# MCU_Power_Clock_Debug.net
KiCad netlist of a schematic drawn in Altium Designer
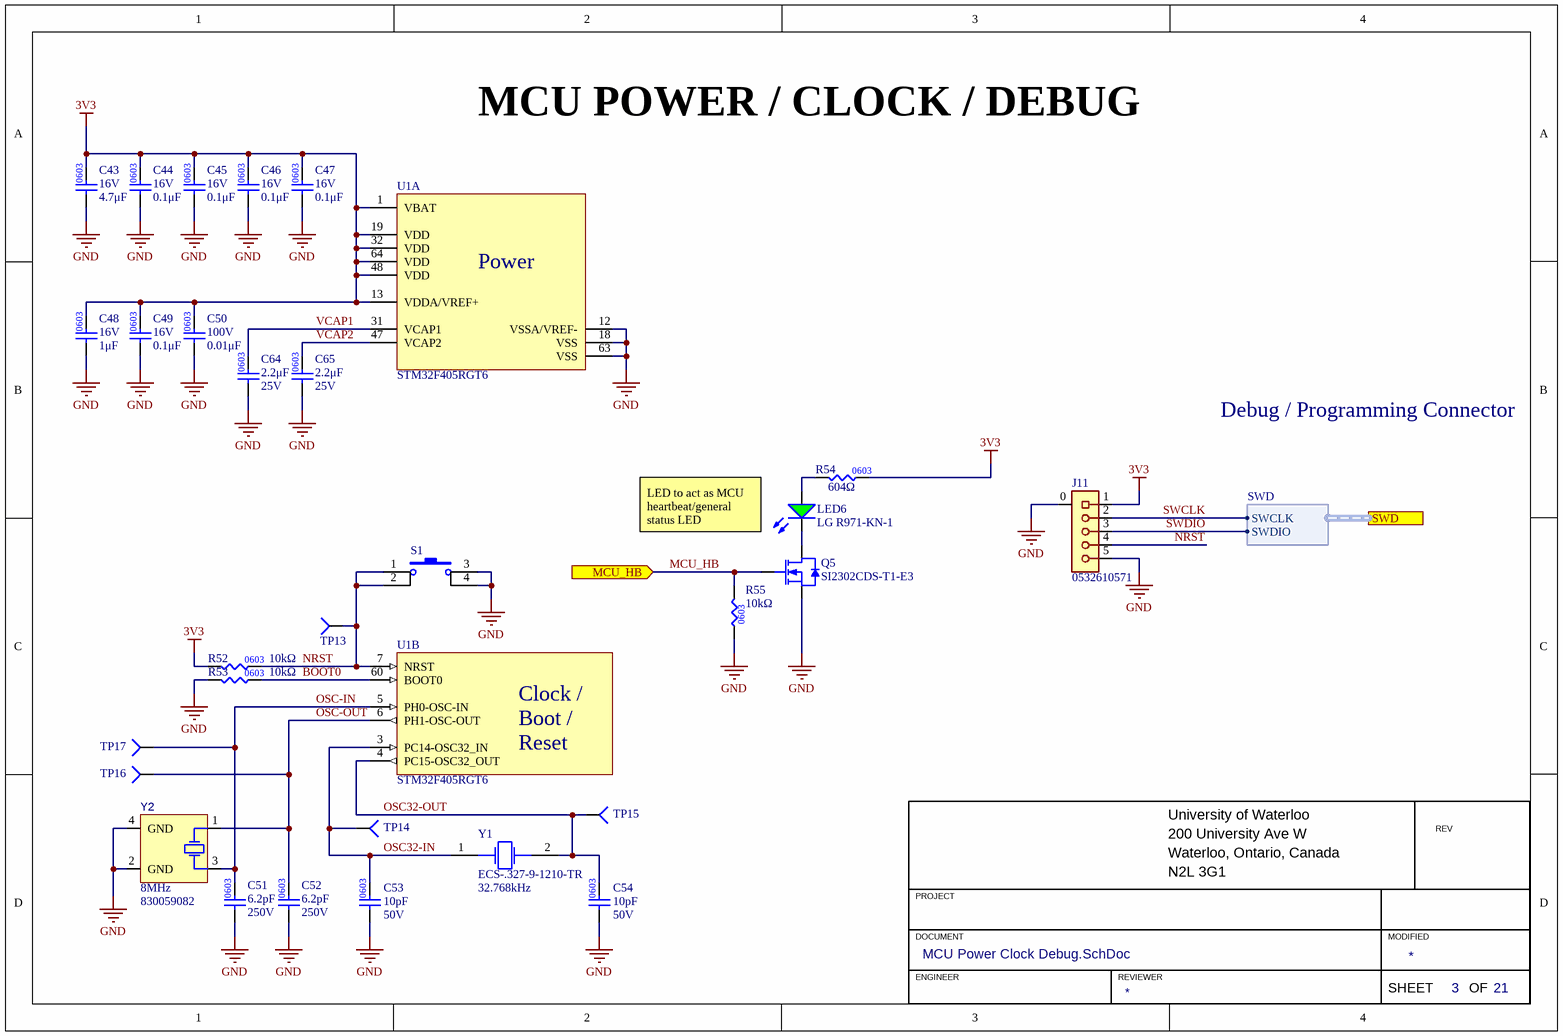
[diagram p0: MCU Power Clock Debug.SchDoc]

(export (version "E")
  (design (tool "Eeschema 10.0.6"))
  (components
    (comp (ref "C43")
      (value "4.7μF")
      (footprint "CAP0603")
      (description "CAP CER 4.7UF 16V X6S 0603")
      (fields (field (name "VOLTAGE RATING") "16V") (field (name "Comment") "CAP_4.7uF_16V_0603"))
      (libsource (lib "Personal_Schematic_Library_2022") (part "CAP_4.7uF_16V_0603"))
    )
    (comp (ref "C44")
      (value "0.1μF")
      (footprint "CAP0603")
      (description "CAP CER 0.1UF 16V X7R 0603")
      (fields (field (name "VOLTAGE RATING") "16V") (field (name "Comment") "CAP_0.1uF_16V_0603"))
      (libsource (lib "Personal_Schematic_Library_2022") (part "CAP_0.1uF_16V_0603"))
    )
    (comp (ref "C45")
      (value "0.1μF")
      (footprint "CAP0603")
      (description "CAP CER 0.1UF 16V X7R 0603")
      (fields (field (name "VOLTAGE RATING") "16V") (field (name "Comment") "CAP_0.1uF_16V_0603"))
      (libsource (lib "Personal_Schematic_Library_2022") (part "CAP_0.1uF_16V_0603"))
    )
    (comp (ref "C46")
      (value "0.1μF")
      (footprint "CAP0603")
      (description "CAP CER 0.1UF 16V X7R 0603")
      (fields (field (name "VOLTAGE RATING") "16V") (field (name "Comment") "CAP_0.1uF_16V_0603"))
      (libsource (lib "Personal_Schematic_Library_2022") (part "CAP_0.1uF_16V_0603"))
    )
    (comp (ref "C47")
      (value "0.1μF")
      (footprint "CAP0603")
      (description "CAP CER 0.1UF 16V X7R 0603")
      (fields (field (name "VOLTAGE RATING") "16V") (field (name "Comment") "CAP_0.1uF_16V_0603"))
      (libsource (lib "Personal_Schematic_Library_2022") (part "CAP_0.1uF_16V_0603"))
    )
    (comp (ref "C48")
      (value "1μF")
      (footprint "CAP0603")
      (description "CAP CER 1UF 16V X7R 0603")
      (fields (field (name "VOLTAGE RATING") "16V") (field (name "Comment") "CAP_1uF_16V_0603"))
      (libsource (lib "Personal_Schematic_Library_2022") (part "CAP_1uF_16V_0603"))
    )
    (comp (ref "C49")
      (value "0.1μF")
      (footprint "CAP0603")
      (description "CAP CER 0.1UF 16V X7R 0603")
      (fields (field (name "VOLTAGE RATING") "16V") (field (name "Comment") "CAP_0.1uF_16V_0603"))
      (libsource (lib "Personal_Schematic_Library_2022") (part "CAP_0.1uF_16V_0603"))
    )
    (comp (ref "C50")
      (value "0.01μF")
      (footprint "CAP0603")
      (description "CAP CER 0.01uF 100V X7R 0603")
      (fields (field (name "VOLTAGE RATING") "100V") (field (name "Comment") "CAP_0.01uF_100V_0603"))
      (libsource (lib "Personal_Schematic_Library_2022") (part "CAP_0.01uF_100V_0603"))
    )
    (comp (ref "C51")
      (value "6.2pF")
      (footprint "CAP0603")
      (description "HVCAP0603 COG 6.2PF .25PF 250V")
      (fields (field (name "VOLTAGE RATING") "250V") (field (name "Comment") "CAP_6.2pF_250V_0603"))
      (libsource (lib "Personal_Schematic_Library_2022") (part "CAP_6.2pF_250V_0603"))
    )
    (comp (ref "C52")
      (value "6.2pF")
      (footprint "CAP0603")
      (description "HVCAP0603 COG 6.2PF .25PF 250V")
      (fields (field (name "VOLTAGE RATING") "250V") (field (name "Comment") "CAP_6.2pF_250V_0603"))
      (libsource (lib "Personal_Schematic_Library_2022") (part "CAP_6.2pF_250V_0603"))
    )
    (comp (ref "C53")
      (value "10pF")
      (footprint "CAP0603")
      (description "CAP CER 10PF 50V X7R 0603")
      (fields (field (name "VOLTAGE RATING") "50V") (field (name "Comment") "CAP_10pF_50V_0603"))
      (libsource (lib "Personal_Schematic_Library_2022") (part "CAP_10pF_50V_0603"))
    )
    (comp (ref "C54")
      (value "10pF")
      (footprint "CAP0603")
      (description "CAP CER 10PF 50V X7R 0603")
      (fields (field (name "VOLTAGE RATING") "50V") (field (name "Comment") "CAP_10pF_50V_0603"))
      (libsource (lib "Personal_Schematic_Library_2022") (part "CAP_10pF_50V_0603"))
    )
    (comp (ref "C64")
      (value "2.2μF")
      (footprint "CAP0603")
      (description "CAP CER 2.2UF 25V X5R 0603")
      (fields (field (name "VOLTAGE RATING") "25V") (field (name "Comment") "CAP_2.2uF_25V_0603"))
      (libsource (lib "Personal_Schematic_Library_2022") (part "CAP_2.2uF_25V_0603"))
    )
    (comp (ref "C65")
      (value "2.2μF")
      (footprint "CAP0603")
      (description "CAP CER 2.2UF 25V X5R 0603")
      (fields (field (name "VOLTAGE RATING") "25V") (field (name "Comment") "CAP_2.2uF_25V_0603"))
      (libsource (lib "Personal_Schematic_Library_2022") (part "CAP_2.2uF_25V_0603"))
    )
    (comp (ref "J11")
      (value "CON_MOLEX-PICO_5POS_RA")
      (footprint "MOLEX-532610571")
      (description "CONN HEADER SMD R/A 5POS 1.25MM")
      (fields (field (name "MANUFACTURER PART NUMBER 1") "0532610571"))
      (libsource (lib "Personal_Schematic_Library_2022") (part "CON_MOLEX-PICO_5POS_RA"))
    )
    (comp (ref "LED6")
      (value "LED_GREEN")
      (footprint "LED_0805_GREEN")
      (description "LED GREEN DIFFUSED 0805 SMD")
      (fields (field (name "MANUFACTURER PART NUMBER 1") "LG R971-KN-1"))
      (libsource (lib "Personal_Schematic_Library_2022") (part "LED_GREEN"))
    )
    (comp (ref "Q5")
      (value "NMOS_20V_6A")
      (footprint "SOT23-3")
      (description "MOSFET N-CH 20V 2.6A SOT23-3")
      (fields (field (name "MANUFACTURER PART NUMBER 1") "SI2302CDS-T1-E3"))
      (libsource (lib "Personal_Schematic_Library_2022") (part "NMOS_20V_2.6A"))
    )
    (comp (ref "R52")
      (value "10kΩ")
      (footprint "RES0603")
      (description "RES 10K OHM 1% 1/8W 0603")
      (fields (field (name "Comment") "RES_10kΩ_0603_1%"))
      (libsource (lib "Personal_Schematic_Library_2022") (part "RES_10kΩ_0603_1%"))
    )
    (comp (ref "R53")
      (value "10kΩ")
      (footprint "RES0603")
      (description "RES 10K OHM 1% 1/8W 0603")
      (fields (field (name "Comment") "RES_10kΩ_0603_1%"))
      (libsource (lib "Personal_Schematic_Library_2022") (part "RES_10kΩ_0603_1%"))
    )
    (comp (ref "R54")
      (value "604Ω")
      (footprint "RES0603")
      (description "RES 604 OHM 1% 1/10W 0603")
      (fields (field (name "Comment") "RES_604Ω_0603_1%"))
      (libsource (lib "Personal_Schematic_Library_2022") (part "RES_604Ω_0603_1%"))
    )
    (comp (ref "R55")
      (value "10kΩ")
      (footprint "RES0603")
      (description "RES 10K OHM 1% 1/8W 0603")
      (fields (field (name "Comment") "RES_10kΩ_0603_1%"))
      (libsource (lib "Personal_Schematic_Library_2022") (part "RES_10kΩ_0603_1%"))
    )
    (comp (ref "S1")
      (value "SW_SPST_NO_4.5x4.5")
      (footprint "SPST_PUSHBUTTON_TL3305AF260QG")
      (description "SWITCH TACTILE SPST-NO 50MA 12V")
      (libsource (lib "Personal_Schematic_Library_2022") (part "SW_SPST_NO_4.5x4.5"))
    )
    (comp (ref "TP13")
      (value "TESTPOINT_1MM_CIRCLE")
      (footprint "TESTPOINT_CIRCLE_1MM")
      (description "TESTPOINT 1MM CIRCLE")
      (libsource (lib "Personal_Schematic_Library_2022") (part "TESTPOINT_1MM_CIRCLE"))
    )
    (comp (ref "TP14")
      (value "TESTPOINT_1MM_CIRCLE")
      (footprint "TESTPOINT_CIRCLE_1MM")
      (description "TESTPOINT 1MM CIRCLE")
      (libsource (lib "Personal_Schematic_Library_2022") (part "TESTPOINT_1MM_CIRCLE"))
    )
    (comp (ref "TP15")
      (value "TESTPOINT_1MM_CIRCLE")
      (footprint "TESTPOINT_CIRCLE_1MM")
      (description "TESTPOINT 1MM CIRCLE")
      (libsource (lib "Personal_Schematic_Library_2022") (part "TESTPOINT_1MM_CIRCLE"))
    )
    (comp (ref "TP16")
      (value "TESTPOINT_1MM_CIRCLE")
      (footprint "TESTPOINT_CIRCLE_1MM")
      (description "TESTPOINT 1MM CIRCLE")
      (libsource (lib "Personal_Schematic_Library_2022") (part "TESTPOINT_1MM_CIRCLE"))
    )
    (comp (ref "TP17")
      (value "TESTPOINT_1MM_CIRCLE")
      (footprint "TESTPOINT_CIRCLE_1MM")
      (description "TESTPOINT 1MM CIRCLE")
      (libsource (lib "Personal_Schematic_Library_2022") (part "TESTPOINT_1MM_CIRCLE"))
    )
    (comp (ref "U1")
      (value "STM32F405RGT6")
      (footprint "STM_LQFP64")
      (description "IC MCU 32BIT 1MB FLASH 64LQFP")
      (libsource (lib "Personal_Schematic_Library_2022") (part "STM32F405RGT6"))
    )
    (comp (ref "Y1")
      (value "CRYSTAL_32.768KHZ")
      (footprint "OSC_ECS-327TR-2")
      (description "CRYSTAL 32.7680KHZ 9PF SMD")
      (fields
        (field (name "FREQUENCY") "32.768kHz")
        (field (name "MANUFACTURER PART NUMBER 1") "ECS-.327-9-1210-TR")
      )
      (libsource (lib "Personal_Schematic_Library_2022") (part "CRYSTAL_32.768KHZ"))
    )
    (comp (ref "Y2")
      (value "CRYSTAL_8MHZ_8PF")
      (footprint "XTAL_WURTH_830059082")
      (description "WE-XTAL QUARTZ CRYSTAL 8.0 MHZ;")
      (fields (field (name "FREQUENCY") "8MHz") (field (name "MANUFACTURER PART NUMBER 1") "830059082"))
      (libsource (lib "Personal_Schematic_Library_2022") (part "CRYSTAL_8MHZ_8PF"))
    )
  )
  (nets
    (net (code "2") (name "/BOOT0") (class "Default")
      (node (ref "R53") (pin "2") (pinfunction "2_2") (pintype "passive"))
      (node (ref "U1") (pin "60") (pinfunction "BOOT0_60") (pintype "input"))
    )
    (net (code "3") (name "/MCU_HB") (class "Default")
      (node (ref "Q5") (pin "1") (pinfunction "GATE_1") (pintype "passive"))
      (node (ref "R55") (pin "2") (pinfunction "2_2") (pintype "passive"))
    )
    (net (code "4") (name "/NRST") (class "Default")
      (node (ref "J11") (pin "4") (pinfunction "4_4") (pintype "passive"))
      (node (ref "R52") (pin "2") (pinfunction "2_2") (pintype "passive"))
      (node (ref "S1") (pin "1") (pinfunction "1_1") (pintype "passive"))
      (node (ref "S1") (pin "2") (pinfunction "2_2") (pintype "passive"))
      (node (ref "TP13") (pin "1") (pinfunction "=value_1") (pintype "passive"))
      (node (ref "U1") (pin "7") (pinfunction "NRST_7") (pintype "input"))
    )
    (net (code "5") (name "/OSC-IN") (class "Default")
      (node (ref "C51") (pin "2") (pinfunction "2_2") (pintype "passive"))
      (node (ref "TP17") (pin "1") (pinfunction "=value_1") (pintype "passive"))
      (node (ref "U1") (pin "5") (pinfunction "PH0-OSC-IN_5") (pintype "input"))
      (node (ref "Y2") (pin "3") (pinfunction "HOT_3") (pintype "passive"))
    )
    (net (code "6") (name "/OSC-OUT") (class "Default")
      (node (ref "C52") (pin "2") (pinfunction "2_2") (pintype "passive"))
      (node (ref "TP16") (pin "1") (pinfunction "=value_1") (pintype "passive"))
      (node (ref "U1") (pin "6") (pinfunction "PH1-OSC-OUT_6") (pintype "output"))
      (node (ref "Y2") (pin "1") (pinfunction "HOT_1") (pintype "passive"))
    )
    (net (code "7") (name "/OSC32-IN") (class "Default")
      (node (ref "C53") (pin "2") (pinfunction "2_2") (pintype "passive"))
      (node (ref "TP14") (pin "1") (pinfunction "=value_1") (pintype "passive"))
      (node (ref "U1") (pin "3") (pinfunction "PC14-OSC32_IN_3") (pintype "input"))
      (node (ref "Y1") (pin "1") (pinfunction "1_1") (pintype "passive"))
    )
    (net (code "8") (name "/OSC32-OUT") (class "Default")
      (node (ref "C54") (pin "2") (pinfunction "2_2") (pintype "passive"))
      (node (ref "TP15") (pin "1") (pinfunction "=value_1") (pintype "passive"))
      (node (ref "U1") (pin "4") (pinfunction "PC15-OSC32_OUT_4") (pintype "output"))
      (node (ref "Y1") (pin "2") (pinfunction "2_2") (pintype "passive"))
    )
    (net (code "9") (name "/SWCLK") (class "Default")
      (node (ref "J11") (pin "2") (pinfunction "2_2") (pintype "passive"))
    )
    (net (code "10") (name "/SWDIO") (class "Default")
      (node (ref "J11") (pin "3") (pinfunction "3_3") (pintype "passive"))
    )
    (net (code "11") (name "/VCAP1") (class "Default")
      (node (ref "C64") (pin "2") (pinfunction "2_2") (pintype "passive"))
      (node (ref "U1") (pin "31") (pinfunction "VCAP1_31") (pintype "power_in"))
    )
    (net (code "12") (name "/VCAP2") (class "Default")
      (node (ref "C65") (pin "2") (pinfunction "2_2") (pintype "passive"))
      (node (ref "U1") (pin "47") (pinfunction "VCAP2_47") (pintype "power_in"))
    )
    (net (code "14") (name "3V3") (class "Default")
      (node (ref "C43") (pin "2") (pinfunction "2_2") (pintype "passive"))
      (node (ref "C44") (pin "2") (pinfunction "2_2") (pintype "passive"))
      (node (ref "C45") (pin "2") (pinfunction "2_2") (pintype "passive"))
      (node (ref "C46") (pin "2") (pinfunction "2_2") (pintype "passive"))
      (node (ref "C47") (pin "2") (pinfunction "2_2") (pintype "passive"))
      (node (ref "C48") (pin "2") (pinfunction "2_2") (pintype "passive"))
      (node (ref "C49") (pin "2") (pinfunction "2_2") (pintype "passive"))
      (node (ref "C50") (pin "2") (pinfunction "2_2") (pintype "passive"))
      (node (ref "J11") (pin "1") (pinfunction "1_1") (pintype "passive"))
      (node (ref "R52") (pin "1") (pinfunction "1_1") (pintype "passive"))
      (node (ref "R54") (pin "2") (pinfunction "2_2") (pintype "passive"))
      (node (ref "U1") (pin "1") (pinfunction "VBAT_1") (pintype "power_in"))
      (node (ref "U1") (pin "13") (pinfunction "VDDA/VREF+_13") (pintype "power_in"))
      (node (ref "U1") (pin "19") (pinfunction "VDD_19") (pintype "power_in"))
      (node (ref "U1") (pin "32") (pinfunction "VDD_32") (pintype "power_in"))
      (node (ref "U1") (pin "48") (pinfunction "VDD_48") (pintype "power_in"))
      (node (ref "U1") (pin "64") (pinfunction "VDD_64") (pintype "power_in"))
    )
    (net (code "15") (name "GND") (class "Default")
      (node (ref "C43") (pin "1") (pinfunction "1_1") (pintype "passive"))
      (node (ref "C44") (pin "1") (pinfunction "1_1") (pintype "passive"))
      (node (ref "C45") (pin "1") (pinfunction "1_1") (pintype "passive"))
      (node (ref "C46") (pin "1") (pinfunction "1_1") (pintype "passive"))
      (node (ref "C47") (pin "1") (pinfunction "1_1") (pintype "passive"))
      (node (ref "C48") (pin "1") (pinfunction "1_1") (pintype "passive"))
      (node (ref "C49") (pin "1") (pinfunction "1_1") (pintype "passive"))
      (node (ref "C50") (pin "1") (pinfunction "1_1") (pintype "passive"))
      (node (ref "C51") (pin "1") (pinfunction "1_1") (pintype "passive"))
      (node (ref "C52") (pin "1") (pinfunction "1_1") (pintype "passive"))
      (node (ref "C53") (pin "1") (pinfunction "1_1") (pintype "passive"))
      (node (ref "C54") (pin "1") (pinfunction "1_1") (pintype "passive"))
      (node (ref "C64") (pin "1") (pinfunction "1_1") (pintype "passive"))
      (node (ref "C65") (pin "1") (pinfunction "1_1") (pintype "passive"))
      (node (ref "J11") (pin "0") (pinfunction "0_0") (pintype "passive"))
      (node (ref "J11") (pin "5") (pinfunction "5_5") (pintype "passive"))
      (node (ref "Q5") (pin "2") (pinfunction "SOURCE_2") (pintype "passive"))
      (node (ref "R53") (pin "1") (pinfunction "1_1") (pintype "passive"))
      (node (ref "R55") (pin "1") (pinfunction "1_1") (pintype "passive"))
      (node (ref "S1") (pin "3") (pinfunction "3_3") (pintype "passive"))
      (node (ref "S1") (pin "4") (pinfunction "4_4") (pintype "passive"))
      (node (ref "U1") (pin "12") (pinfunction "VSSA/VREF-_12") (pintype "power_in"))
      (node (ref "U1") (pin "18") (pinfunction "VSS_18") (pintype "power_in"))
      (node (ref "U1") (pin "63") (pinfunction "VSS_63") (pintype "power_in"))
      (node (ref "Y2") (pin "2") (pinfunction "GND_2") (pintype "power_in"))
      (node (ref "Y2") (pin "4") (pinfunction "GND_4") (pintype "power_in"))
    )
    (net (code "16") (name "Net-(LED6-A)") (class "Default")
      (node (ref "LED6") (pin "1") (pinfunction "A_1") (pintype "passive"))
      (node (ref "R54") (pin "1") (pinfunction "1_1") (pintype "passive"))
    )
    (net (code "17") (name "Net-(LED6-K)") (class "Default")
      (node (ref "LED6") (pin "2") (pinfunction "K_2") (pintype "passive"))
      (node (ref "Q5") (pin "3") (pinfunction "DRAIN_3") (pintype "passive"))
    )
  )
)
